# SD.net
KiCad netlist of a schematic drawn in Altium Designer
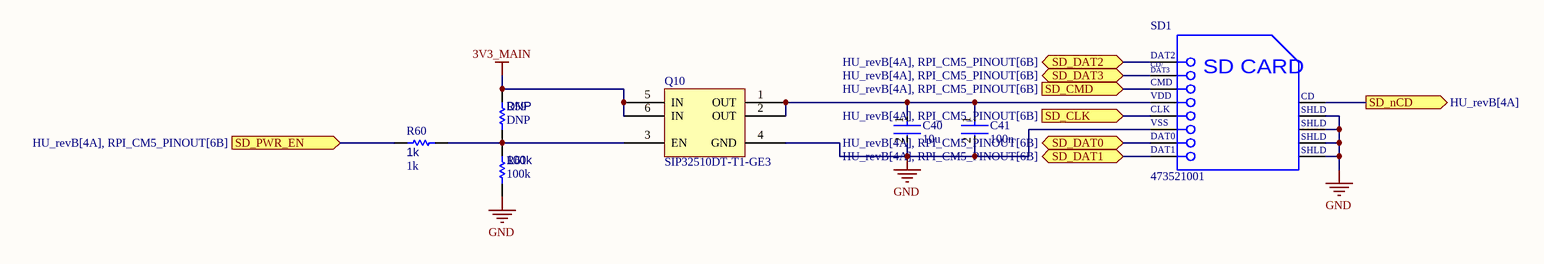
[diagram p0: SD.SchDoc]

(export (version "E")
  (design (tool "Eeschema 10.0.6"))
  (components
    (comp (ref "C40")
      (value "10u")
      (footprint "FP-0402-L_1_0_0_05-W_0_5-IPC_A")
      (description "LARGE PADS, 0402 CAP, CHANGE COMMENT TO MATCH REAL P/N")
      (libsource (lib "Space Concordia") (part "b4654b650e69147ec39a6b967a45e02"))
    )
    (comp (ref "C41")
      (value "100n")
      (footprint "FP-0402-L_1_0_0_05-W_0_5-IPC_A")
      (description "LARGE PADS, 0402 CAP, CHANGE COMMENT TO MATCH REAL P/N")
      (libsource (lib "Space Concordia") (part "b4654b650e69147ec39a6b967a45e02"))
    )
    (comp (ref "Q10")
      (value "SIP32510DT-T1-GE3")
      (footprint "SOT95P284X110-6N")
      (description "Power Switch ICs – Power Distribution; VISHAY; SIP32510DT-T1-GE3; 1; 1; 5.5 V; SOT-23-6")
      (libsource (lib "Space Concordia") (part "SIP32510DT-T1-GE3"))
    )
    (comp (ref "R59")
      (value "DNP")
      (footprint "R0603B")
      (description "Resistor")
      (fields (field (name "ALTIUM_VALUE") "DNP"))
      (libsource (lib "Space Concordia") (part "Resistor"))
    )
    (comp (ref "R60")
      (value "1k")
      (footprint "R0603B")
      (description "Resistor")
      (fields (field (name "ALTIUM_VALUE") "1k"))
      (libsource (lib "Space Concordia") (part "Resistor"))
    )
    (comp (ref "R61")
      (value "100k")
      (footprint "R0603B")
      (description "Resistor")
      (fields (field (name "ALTIUM_VALUE") "100k"))
      (libsource (lib "Space Concordia") (part "Resistor"))
    )
    (comp (ref "SD1")
      (value "473521001")
      (footprint "MOLX-473521001_V")
      (description "MicroSD(TM), Pitch 1.1 mm, 8 Position, Height 1.88 mm, -20 to 85 degC, RoHS, Tape and Reel")
      (fields (field (name "MANUFACTURER") "Molex"))
      (libsource (lib "Altium Content Vault") (part "CN-SD-8-1SW-4S"))
    )
  )
  (nets
    (net (code "1") (name "/SD_CLK") (class "Default")
      (node (ref "SD1") (pin "5") (pinfunction "CLK_5") (pintype "passive"))
    )
    (net (code "2") (name "/SD_CMD") (class "Default")
      (node (ref "SD1") (pin "3") (pinfunction "CMD_3") (pintype "passive"))
    )
    (net (code "3") (name "/SD_DAT0") (class "Default")
      (node (ref "SD1") (pin "7") (pinfunction "DAT0_7") (pintype "passive"))
    )
    (net (code "4") (name "/SD_DAT1") (class "Default")
      (node (ref "SD1") (pin "8") (pinfunction "DAT1_8") (pintype "passive"))
    )
    (net (code "5") (name "/SD_DAT2") (class "Default")
      (node (ref "SD1") (pin "1") (pinfunction "DAT2_1") (pintype "passive"))
    )
    (net (code "6") (name "/SD_DAT3") (class "Default")
      (node (ref "SD1") (pin "2") (pinfunction "CD/DAT3_2") (pintype "passive"))
    )
    (net (code "7") (name "/SD_PWR_EN") (class "Default")
      (node (ref "R60") (pin "2") (pinfunction "2_2") (pintype "passive"))
    )
    (net (code "8") (name "/SD_nCD") (class "Default")
      (node (ref "SD1") (pin "9") (pinfunction "CD_9") (pintype "passive"))
    )
    (net (code "9") (name "3V3_MAIN") (class "Default")
      (node (ref "Q10") (pin "5") (pinfunction "IN_5") (pintype "passive"))
      (node (ref "Q10") (pin "6") (pinfunction "IN_6") (pintype "passive"))
      (node (ref "R59") (pin "2") (pinfunction "2_2") (pintype "passive"))
    )
    (net (code "10") (name "GND") (class "Default")
      (node (ref "C40") (pin "2") (pinfunction "2_2") (pintype "passive"))
      (node (ref "C41") (pin "2") (pinfunction "2_2") (pintype "passive"))
      (node (ref "Q10") (pin "4") (pinfunction "GND_4") (pintype "passive"))
      (node (ref "R61") (pin "1") (pinfunction "1_1") (pintype "passive"))
      (node (ref "SD1") (pin "10") (pinfunction "SHLD_10") (pintype "passive"))
      (node (ref "SD1") (pin "11") (pinfunction "SHLD_11") (pintype "passive"))
      (node (ref "SD1") (pin "12") (pinfunction "SHLD_12") (pintype "passive"))
      (node (ref "SD1") (pin "13") (pinfunction "SHLD_13") (pintype "passive"))
      (node (ref "SD1") (pin "6") (pinfunction "VSS_6") (pintype "passive"))
    )
    (net (code "11") (name "Net-(Q10-EN)") (class "Default")
      (node (ref "Q10") (pin "3") (pinfunction "EN_3") (pintype "passive"))
      (node (ref "R59") (pin "1") (pinfunction "1_1") (pintype "passive"))
      (node (ref "R60") (pin "1") (pinfunction "1_1") (pintype "passive"))
      (node (ref "R61") (pin "2") (pinfunction "2_2") (pintype "passive"))
    )
    (net (code "12") (name "Net-(SD1-VDD)") (class "Default")
      (node (ref "C40") (pin "1") (pinfunction "1_1") (pintype "passive"))
      (node (ref "C41") (pin "1") (pinfunction "1_1") (pintype "passive"))
      (node (ref "Q10") (pin "1") (pinfunction "OUT_1") (pintype "passive"))
      (node (ref "Q10") (pin "2") (pinfunction "OUT_2") (pintype "passive"))
      (node (ref "SD1") (pin "4") (pinfunction "VDD_4") (pintype "passive"))
    )
  )
)
